# PROC054D_AWR_1_AWR_4_LP87524P.net
KiCad netlist of a schematic drawn in Altium Designer
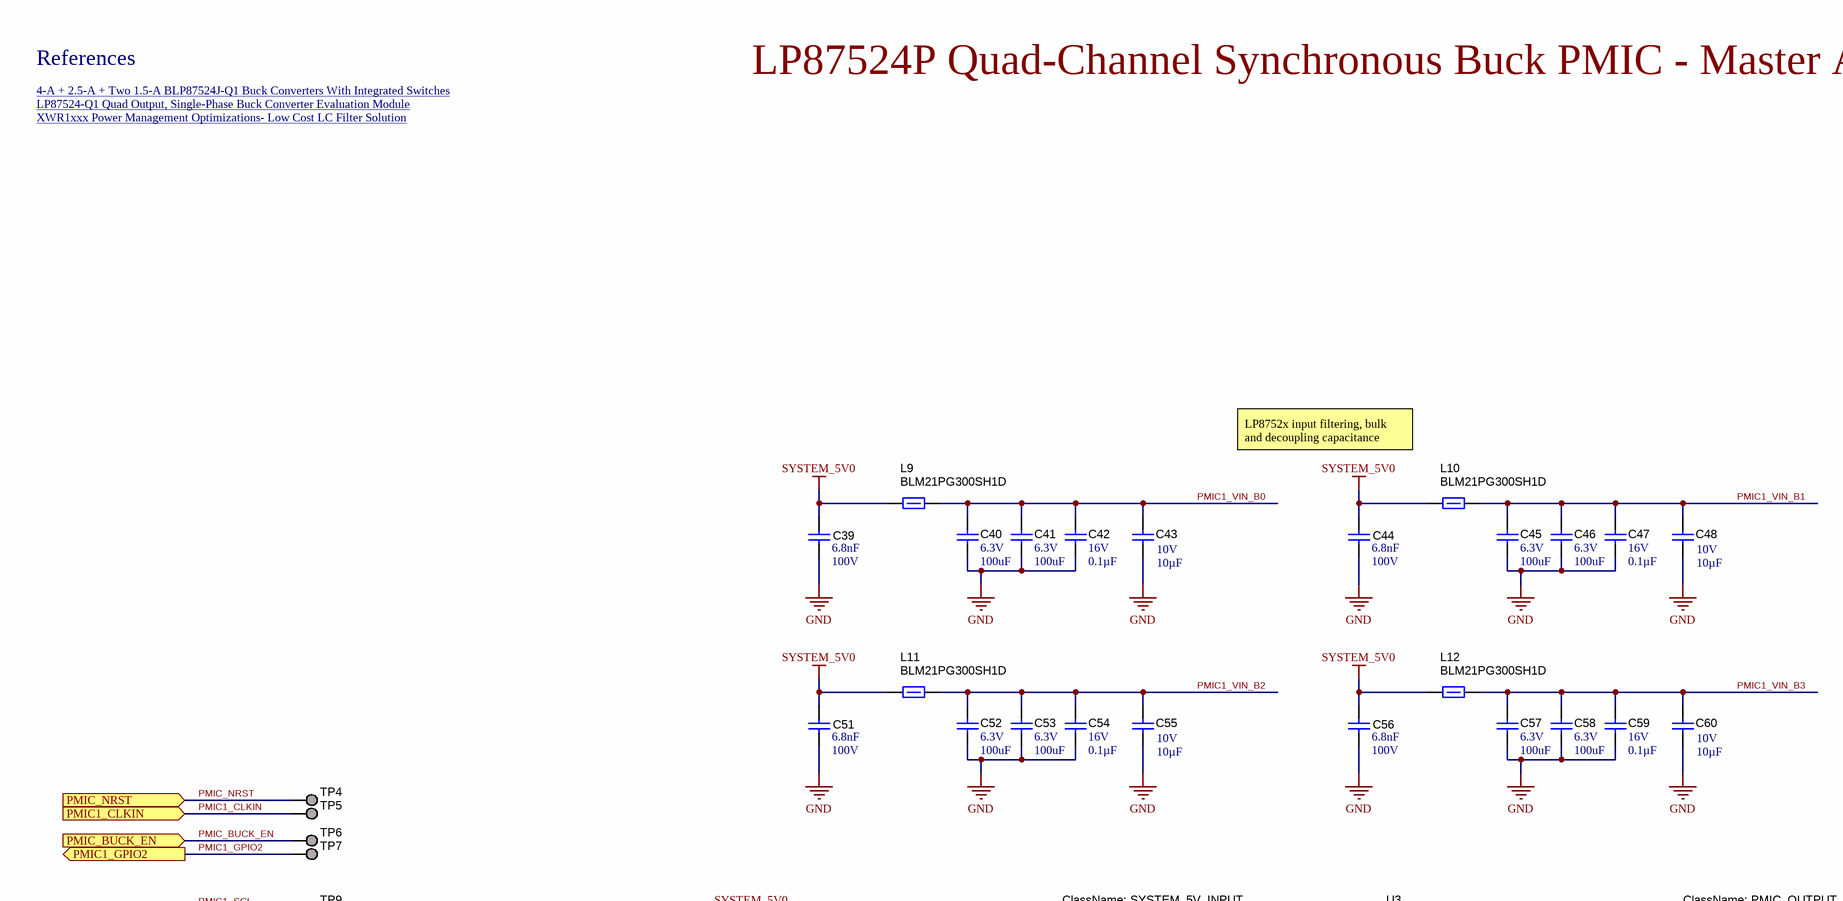
[diagram p0: PROC054D_AWR_1_AWR_4_LP87524P.SchDoc, top left]
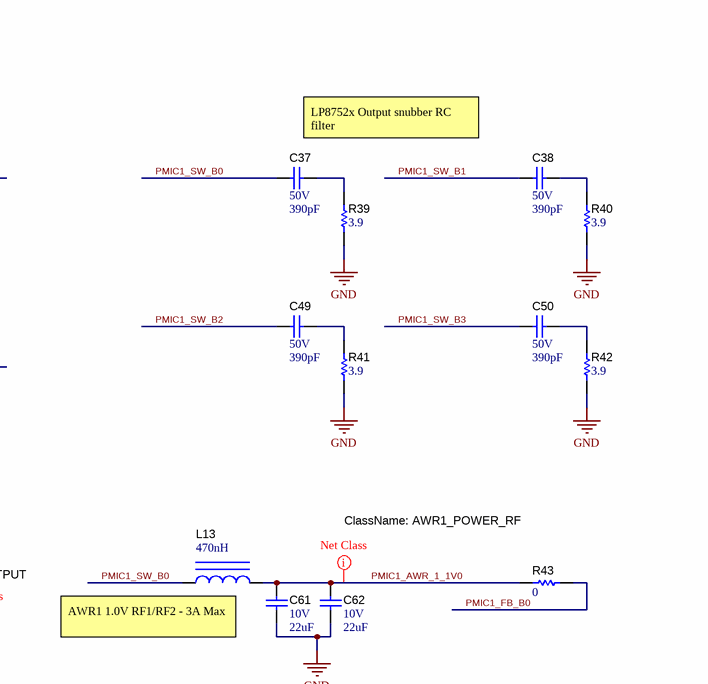
[diagram p1: PROC054D_AWR_1_AWR_4_LP87524P.SchDoc, top right]
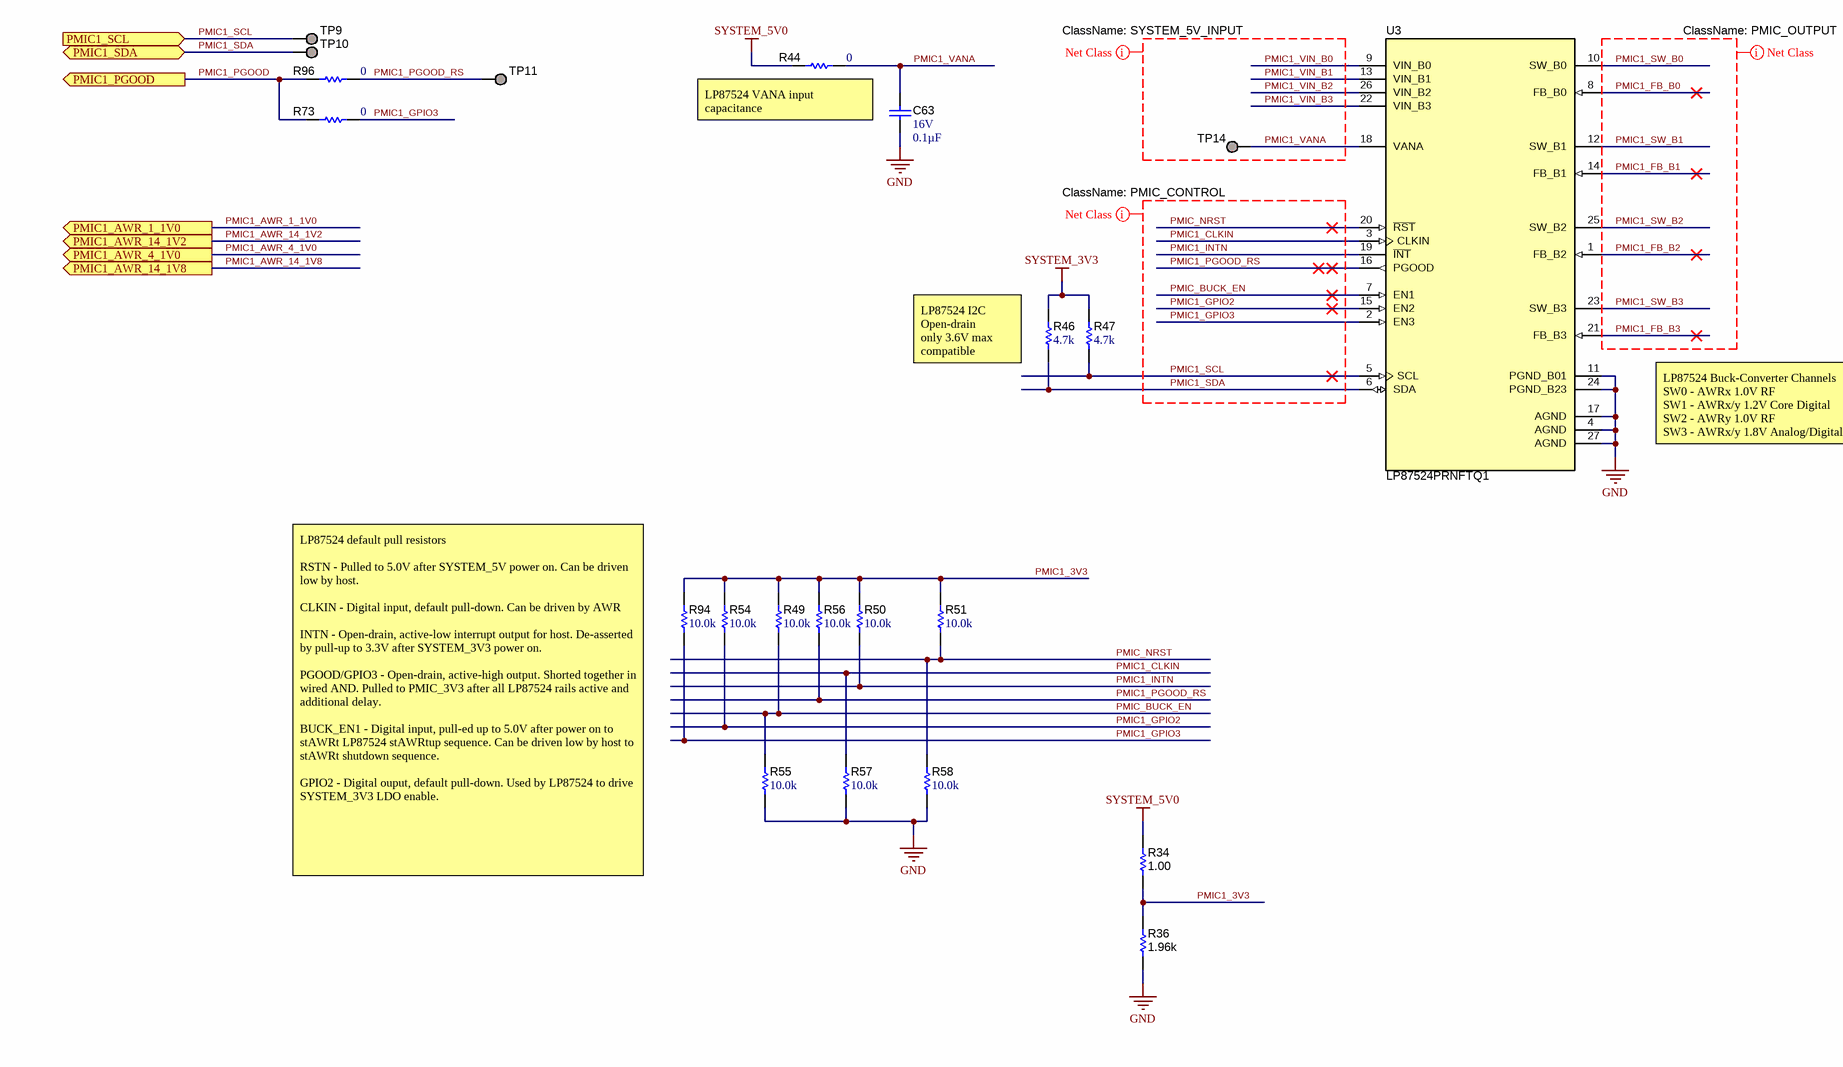
[diagram p2: PROC054D_AWR_1_AWR_4_LP87524P.SchDoc, bottom left]
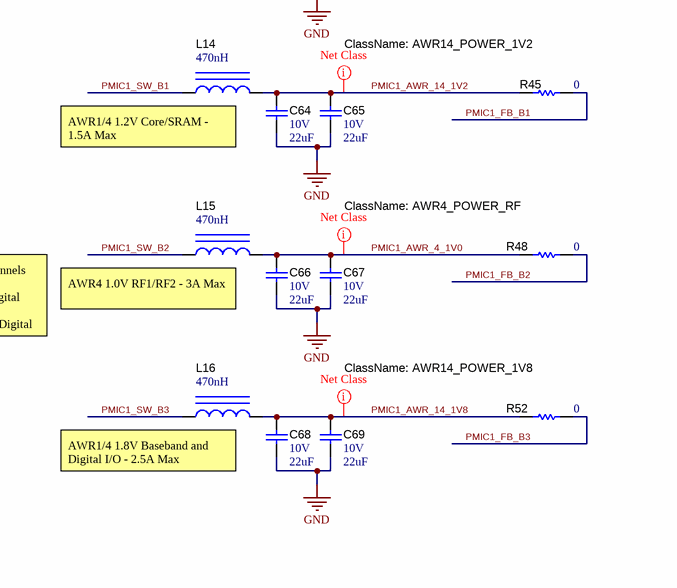
[diagram p3: PROC054D_AWR_1_AWR_4_LP87524P.SchDoc, bottom right]

(export (version "E")
  (design (tool "Eeschema 10.0.6"))
  (components
    (comp (ref "C37")
      (value "GCM155R71H391KA37D")
      (footprint "0402S")
      (description "CAP, CERM, 390 pF, 50 V,+/- 10%, X7R, AEC-Q200 Grade 1, 0402")
      (fields
        (field (name "MANUFACTURER") "MuRata")
        (field (name "VDC_V") "50V")
        (field (name "VALUEDISPLAYED") "390pF")
      )
      (libsource (lib "Altium Vault - TI") (part "Capacitor"))
    )
    (comp (ref "C38")
      (value "GCM155R71H391KA37D")
      (footprint "0402S")
      (description "CAP, CERM, 390 pF, 50 V,+/- 10%, X7R, AEC-Q200 Grade 1, 0402")
      (fields
        (field (name "MANUFACTURER") "MuRata")
        (field (name "VDC_V") "50V")
        (field (name "VALUEDISPLAYED") "390pF")
      )
      (libsource (lib "Altium Vault - TI") (part "Capacitor"))
    )
    (comp (ref "C39")
      (value "GCM188R72A682KA37D")
      (footprint "0603S")
      (description "CAP, CERM, 6800 pF, 100 V,+/- 10%, X7R, AEC-Q200 Grade 1, 0603")
      (fields
        (field (name "CAP_F") "6.8nF")
        (field (name "VDC_V") "100V")
        (field (name "MANUFACTURER") "MuRata")
      )
      (libsource (lib "Altium Vault - TI") (part "Capacitor"))
    )
    (comp (ref "C40")
      (value "GRM21BR60J107M")
      (footprint "0805L")
      (description "CAP, CERM, 100 uF, 6.3 V, +/- 20%, X5R, 0805")
      (fields
        (field (name "MANUFACTURER") "MuRata")
        (field (name "VDC_V") "6.3V")
        (field (name "VALUEDISPLAYED") "100uF")
        (field (name "PUBLISHER") "Texas Instruments")
      )
      (libsource (lib "Altium Vault - TI") (part "CMP-0008280-2"))
    )
    (comp (ref "C41")
      (value "GRM21BR60J107M")
      (footprint "0805L")
      (description "CAP, CERM, 100 uF, 6.3 V, +/- 20%, X5R, 0805")
      (fields
        (field (name "MANUFACTURER") "MuRata")
        (field (name "VDC_V") "6.3V")
        (field (name "VALUEDISPLAYED") "100uF")
        (field (name "PUBLISHER") "Texas Instruments")
      )
      (libsource (lib "Altium Vault - TI") (part "CMP-0008280-2"))
    )
    (comp (ref "C42")
      (value "GCM155R71C104JA55D")
      (footprint "0402S")
      (description "CAP, CERM, 0.1 µF, 16 V,+/- 5%, X7R, AEC-Q200 Grade 1, 0402")
      (fields
        (field (name "MANUFACTURER") "MuRata")
        (field (name "VDC_V") "16V")
        (field (name "VALUEDISPLAYED") "0.1µF")
      )
      (libsource (lib "Altium Vault - TI") (part "CMP-0080702-1"))
    )
    (comp (ref "C43")
      (value "GRM21BR71A106KA73L")
      (footprint "0805L")
      (description "CAP, CERM, 10 µF,  V,+/- 10%, X7R, 0805")
      (fields
        (field (name "MANUFACTURER") "MuRata")
        (field (name "CAP_F") "10µF")
        (field (name "VDC_V") "10V")
      )
      (libsource (lib "Altium Vault - TI") (part "Capacitor"))
    )
    (comp (ref "C44")
      (value "GCM188R72A682KA37D")
      (footprint "0603S")
      (description "CAP, CERM, 6800 pF, 100 V,+/- 10%, X7R, AEC-Q200 Grade 1, 0603")
      (fields
        (field (name "CAP_F") "6.8nF")
        (field (name "VDC_V") "100V")
        (field (name "MANUFACTURER") "MuRata")
      )
      (libsource (lib "Altium Vault - TI") (part "Capacitor"))
    )
    (comp (ref "C45")
      (value "GRM21BR60J107M")
      (footprint "0805L")
      (description "CAP, CERM, 100 uF, 6.3 V, +/- 20%, X5R, 0805")
      (fields
        (field (name "MANUFACTURER") "MuRata")
        (field (name "VDC_V") "6.3V")
        (field (name "VALUEDISPLAYED") "100uF")
        (field (name "PUBLISHER") "Texas Instruments")
      )
      (libsource (lib "Altium Vault - TI") (part "Capacitor"))
    )
    (comp (ref "C46")
      (value "GRM21BR60J107M")
      (footprint "0805L")
      (description "CAP, CERM, 100 uF, 6.3 V, +/- 20%, X5R, 0805")
      (fields
        (field (name "MANUFACTURER") "MuRata")
        (field (name "VDC_V") "6.3V")
        (field (name "VALUEDISPLAYED") "100uF")
        (field (name "PUBLISHER") "Texas Instruments")
      )
      (libsource (lib "Altium Vault - TI") (part "Capacitor"))
    )
    (comp (ref "C47")
      (value "GCM155R71C104JA55D")
      (footprint "0402S")
      (description "CAP, CERM, 0.1 µF, 16 V,+/- 5%, X7R, AEC-Q200 Grade 1, 0402")
      (fields
        (field (name "MANUFACTURER") "MuRata")
        (field (name "VDC_V") "16V")
        (field (name "VALUEDISPLAYED") "0.1µF")
      )
      (libsource (lib "Altium Vault - TI") (part "Capacitor"))
    )
    (comp (ref "C48")
      (value "GRM21BR71A106KA73L")
      (footprint "0805L")
      (description "CAP, CERM, 10 µF,  V,+/- 10%, X7R, 0805")
      (fields
        (field (name "MANUFACTURER") "MuRata")
        (field (name "CAP_F") "10µF")
        (field (name "VDC_V") "10V")
      )
      (libsource (lib "Altium Vault - TI") (part "Capacitor"))
    )
    (comp (ref "C49")
      (value "GCM155R71H391KA37D")
      (footprint "0402S")
      (description "CAP, CERM, 390 pF, 50 V,+/- 10%, X7R, AEC-Q200 Grade 1, 0402")
      (fields
        (field (name "MANUFACTURER") "MuRata")
        (field (name "VDC_V") "50V")
        (field (name "VALUEDISPLAYED") "390pF")
      )
      (libsource (lib "Altium Vault - TI") (part "Capacitor"))
    )
    (comp (ref "C50")
      (value "GCM155R71H391KA37D")
      (footprint "0402S")
      (description "CAP, CERM, 390 pF, 50 V,+/- 10%, X7R, AEC-Q200 Grade 1, 0402")
      (fields
        (field (name "MANUFACTURER") "MuRata")
        (field (name "VDC_V") "50V")
        (field (name "VALUEDISPLAYED") "390pF")
      )
      (libsource (lib "Altium Vault - TI") (part "Capacitor"))
    )
    (comp (ref "C51")
      (value "GCM188R72A682KA37D")
      (footprint "0603S")
      (description "CAP, CERM, 6800 pF, 100 V,+/- 10%, X7R, AEC-Q200 Grade 1, 0603")
      (fields
        (field (name "CAP_F") "6.8nF")
        (field (name "VDC_V") "100V")
        (field (name "MANUFACTURER") "MuRata")
      )
      (libsource (lib "Altium Vault - TI") (part "Capacitor"))
    )
    (comp (ref "C52")
      (value "GRM21BR60J107M")
      (footprint "0805L")
      (description "CAP, CERM, 100 uF, 6.3 V, +/- 20%, X5R, 0805")
      (fields
        (field (name "MANUFACTURER") "MuRata")
        (field (name "VDC_V") "6.3V")
        (field (name "VALUEDISPLAYED") "100uF")
        (field (name "PUBLISHER") "Texas Instruments")
      )
      (libsource (lib "Altium Vault - TI") (part "Capacitor"))
    )
    (comp (ref "C53")
      (value "GRM21BR60J107M")
      (footprint "0805L")
      (description "CAP, CERM, 100 uF, 6.3 V, +/- 20%, X5R, 0805")
      (fields
        (field (name "MANUFACTURER") "MuRata")
        (field (name "VDC_V") "6.3V")
        (field (name "VALUEDISPLAYED") "100uF")
        (field (name "PUBLISHER") "Texas Instruments")
      )
      (libsource (lib "Altium Vault - TI") (part "Capacitor"))
    )
    (comp (ref "C54")
      (value "GCM155R71C104JA55D")
      (footprint "0402S")
      (description "CAP, CERM, 0.1 µF, 16 V,+/- 5%, X7R, AEC-Q200 Grade 1, 0402")
      (fields
        (field (name "MANUFACTURER") "MuRata")
        (field (name "VDC_V") "16V")
        (field (name "VALUEDISPLAYED") "0.1µF")
      )
      (libsource (lib "Altium Vault - TI") (part "Capacitor"))
    )
    (comp (ref "C55")
      (value "GRM21BR71A106KA73L")
      (footprint "0805L")
      (description "CAP, CERM, 10 µF,  V,+/- 10%, X7R, 0805")
      (fields
        (field (name "MANUFACTURER") "MuRata")
        (field (name "CAP_F") "10µF")
        (field (name "VDC_V") "10V")
      )
      (libsource (lib "Altium Vault - TI") (part "Capacitor"))
    )
    (comp (ref "C56")
      (value "GCM188R72A682KA37D")
      (footprint "0603S")
      (description "CAP, CERM, 6800 pF, 100 V,+/- 10%, X7R, AEC-Q200 Grade 1, 0603")
      (fields
        (field (name "CAP_F") "6.8nF")
        (field (name "VDC_V") "100V")
        (field (name "MANUFACTURER") "MuRata")
      )
      (libsource (lib "Altium Vault - TI") (part "Capacitor"))
    )
    (comp (ref "C57")
      (value "GRM21BR60J107M")
      (footprint "0805L")
      (description "CAP, CERM, 100 uF, 6.3 V, +/- 20%, X5R, 0805")
      (fields
        (field (name "MANUFACTURER") "MuRata")
        (field (name "VDC_V") "6.3V")
        (field (name "VALUEDISPLAYED") "100uF")
        (field (name "PUBLISHER") "Texas Instruments")
      )
      (libsource (lib "Altium Vault - TI") (part "Capacitor"))
    )
    (comp (ref "C58")
      (value "GRM21BR60J107M")
      (footprint "0805L")
      (description "CAP, CERM, 100 uF, 6.3 V, +/- 20%, X5R, 0805")
      (fields
        (field (name "MANUFACTURER") "MuRata")
        (field (name "VDC_V") "6.3V")
        (field (name "VALUEDISPLAYED") "100uF")
        (field (name "PUBLISHER") "Texas Instruments")
      )
      (libsource (lib "Altium Vault - TI") (part "Capacitor"))
    )
    (comp (ref "C59")
      (value "GCM155R71C104JA55D")
      (footprint "0402S")
      (description "CAP, CERM, 0.1 µF, 16 V,+/- 5%, X7R, AEC-Q200 Grade 1, 0402")
      (fields
        (field (name "MANUFACTURER") "MuRata")
        (field (name "VDC_V") "16V")
        (field (name "VALUEDISPLAYED") "0.1µF")
      )
      (libsource (lib "Altium Vault - TI") (part "Capacitor"))
    )
    (comp (ref "C60")
      (value "GRM21BR71A106KA73L")
      (footprint "0805L")
      (description "CAP, CERM, 10 µF,  V,+/- 10%, X7R, 0805")
      (fields
        (field (name "MANUFACTURER") "MuRata")
        (field (name "CAP_F") "10µF")
        (field (name "VDC_V") "10V")
      )
      (libsource (lib "Altium Vault - TI") (part "Capacitor"))
    )
    (comp (ref "C61")
      (value "C2012X7S1A226M125AC")
      (footprint "0805L")
      (description "CAP, CERM, 22 uF, 10 V, +/- 20%, X7S, 0805")
      (fields
        (field (name "MANUFACTURER") "TDK")
        (field (name "VDC_V") "10V")
        (field (name "VALUEDISPLAYED") "22uF")
        (field (name "PUBLISHER") "Texas Instruments")
      )
      (libsource (lib "Altium Vault - TI") (part "Capacitor"))
    )
    (comp (ref "C62")
      (value "C2012X7S1A226M125AC")
      (footprint "0805L")
      (description "CAP, CERM, 22 uF, 10 V, +/- 20%, X7S, 0805")
      (fields
        (field (name "MANUFACTURER") "TDK")
        (field (name "VDC_V") "10V")
        (field (name "VALUEDISPLAYED") "22uF")
        (field (name "PUBLISHER") "Texas Instruments")
      )
      (libsource (lib "Altium Vault - TI") (part "Capacitor"))
    )
    (comp (ref "C63")
      (value "GCM155R71C104JA55D")
      (footprint "0402S")
      (description "CAP, CERM, 0.1 µF, 16 V,+/- 5%, X7R, AEC-Q200 Grade 1, 0402")
      (fields
        (field (name "MANUFACTURER") "MuRata")
        (field (name "VDC_V") "16V")
        (field (name "VALUEDISPLAYED") "0.1µF")
      )
      (libsource (lib "Altium Vault - TI") (part "CMP-0080702-1"))
    )
    (comp (ref "C64")
      (value "C2012X7S1A226M125AC")
      (footprint "0805L")
      (description "CAP, CERM, 22 uF, 10 V, +/- 20%, X7S, 0805")
      (fields
        (field (name "MANUFACTURER") "TDK")
        (field (name "VDC_V") "10V")
        (field (name "VALUEDISPLAYED") "22uF")
        (field (name "PUBLISHER") "Texas Instruments")
      )
      (libsource (lib "Altium Vault - TI") (part "Capacitor"))
    )
    (comp (ref "C65")
      (value "C2012X7S1A226M125AC")
      (footprint "0805L")
      (description "CAP, CERM, 22 uF, 10 V, +/- 20%, X7S, 0805")
      (fields
        (field (name "MANUFACTURER") "TDK")
        (field (name "VDC_V") "10V")
        (field (name "VALUEDISPLAYED") "22uF")
        (field (name "PUBLISHER") "Texas Instruments")
      )
      (libsource (lib "Altium Vault - TI") (part "Capacitor"))
    )
    (comp (ref "C66")
      (value "C2012X7S1A226M125AC")
      (footprint "0805L")
      (description "CAP, CERM, 22 uF, 10 V, +/- 20%, X7S, 0805")
      (fields
        (field (name "MANUFACTURER") "TDK")
        (field (name "VDC_V") "10V")
        (field (name "VALUEDISPLAYED") "22uF")
        (field (name "PUBLISHER") "Texas Instruments")
      )
      (libsource (lib "Altium Vault - TI") (part "Capacitor"))
    )
    (comp (ref "C67")
      (value "C2012X7S1A226M125AC")
      (footprint "0805L")
      (description "CAP, CERM, 22 uF, 10 V, +/- 20%, X7S, 0805")
      (fields
        (field (name "MANUFACTURER") "TDK")
        (field (name "VDC_V") "10V")
        (field (name "VALUEDISPLAYED") "22uF")
        (field (name "PUBLISHER") "Texas Instruments")
      )
      (libsource (lib "Altium Vault - TI") (part "Capacitor"))
    )
    (comp (ref "C68")
      (value "C2012X7S1A226M125AC")
      (footprint "0805L")
      (description "CAP, CERM, 22 uF, 10 V, +/- 20%, X7S, 0805")
      (fields
        (field (name "MANUFACTURER") "TDK")
        (field (name "VDC_V") "10V")
        (field (name "VALUEDISPLAYED") "22uF")
        (field (name "PUBLISHER") "Texas Instruments")
      )
      (libsource (lib "Altium Vault - TI") (part "Capacitor"))
    )
    (comp (ref "C69")
      (value "C2012X7S1A226M125AC")
      (footprint "0805L")
      (description "CAP, CERM, 22 uF, 10 V, +/- 20%, X7S, 0805")
      (fields
        (field (name "MANUFACTURER") "TDK")
        (field (name "VDC_V") "10V")
        (field (name "VALUEDISPLAYED") "22uF")
        (field (name "PUBLISHER") "Texas Instruments")
      )
      (libsource (lib "Altium Vault - TI") (part "Capacitor"))
    )
    (comp (ref "L9")
      (value "BLM21PG300SH1D")
      (footprint "0805_HV")
      (description "Ferrite Bead, 30 ohm @ 100 MHz, 4 A, 0805")
      (fields (field (name "MANUFACTURER") "MuRata") (field (name "PUBLISHER") "Texas Instruments"))
      (libsource (lib "Altium Vault - TI") (part "CMP-0003364-1"))
    )
    (comp (ref "L10")
      (value "BLM21PG300SH1D")
      (footprint "0805_HV")
      (description "Ferrite Bead, 30 ohm @ 100 MHz, 4 A, 0805")
      (fields (field (name "MANUFACTURER") "MuRata") (field (name "PUBLISHER") "Texas Instruments"))
      (libsource (lib "Altium Vault - TI") (part "Ferrite_Bead"))
    )
    (comp (ref "L11")
      (value "BLM21PG300SH1D")
      (footprint "0805_HV")
      (description "Ferrite Bead, 30 ohm @ 100 MHz, 4 A, 0805")
      (fields (field (name "MANUFACTURER") "MuRata") (field (name "PUBLISHER") "Texas Instruments"))
      (libsource (lib "Altium Vault - TI") (part "Ferrite_Bead"))
    )
    (comp (ref "L12")
      (value "BLM21PG300SH1D")
      (footprint "0805_HV")
      (description "Ferrite Bead, 30 ohm @ 100 MHz, 4 A, 0805")
      (fields (field (name "MANUFACTURER") "MuRata") (field (name "PUBLISHER") "Texas Instruments"))
      (libsource (lib "Altium Vault - TI") (part "Ferrite_Bead"))
    )
    (comp (ref "L13")
      (value "DFE252012PD-R47M")
      (footprint "DFE252012P")
      (description "Inductor, Shielded, 470 nH, 4.7 A, 0.021 ohm, SMD")
      (fields
        (field (name "MANUFACTURER") "MuRata Toko")
        (field (name "VALUEDISPLAYED") "470nH")
        (field (name "PUBLISHER") "Texas Instruments")
      )
      (libsource (lib "Altium Vault - TI") (part "Inductor_Iron"))
    )
    (comp (ref "L14")
      (value "DFE252012PD-R47M")
      (footprint "DFE252012P")
      (description "Inductor, Shielded, 470 nH, 4.7 A, 0.021 ohm, SMD")
      (fields
        (field (name "MANUFACTURER") "MuRata Toko")
        (field (name "VALUEDISPLAYED") "470nH")
        (field (name "PUBLISHER") "Texas Instruments")
      )
      (libsource (lib "Altium Vault - TI") (part "Inductor_Iron"))
    )
    (comp (ref "L15")
      (value "DFE252012PD-R47M")
      (footprint "DFE252012P")
      (description "Inductor, Shielded, 470 nH, 4.7 A, 0.021 ohm, SMD")
      (fields
        (field (name "MANUFACTURER") "MuRata Toko")
        (field (name "VALUEDISPLAYED") "470nH")
        (field (name "PUBLISHER") "Texas Instruments")
      )
      (libsource (lib "Altium Vault - TI") (part "Inductor_Iron"))
    )
    (comp (ref "L16")
      (value "DFE252012PD-R47M")
      (footprint "DFE252012P")
      (description "Inductor, Shielded, 470 nH, 4.7 A, 0.021 ohm, SMD")
      (fields
        (field (name "MANUFACTURER") "MuRata Toko")
        (field (name "VALUEDISPLAYED") "470nH")
        (field (name "PUBLISHER") "Texas Instruments")
      )
      (libsource (lib "Altium Vault - TI") (part "Inductor_Iron"))
    )
    (comp (ref "R34")
      (value "CRCW06031R00FKEA")
      (footprint "0603")
      (description "RES, 1.00, 1%, 0.1 W, AEC-Q200 Grade 0, 0603")
      (fields (field (name "MANUFACTURER") "Vishay-Dale") (field (name "VALUEDISPLAYED") "1.00"))
      (libsource (lib "Altium Vault - TI") (part "Resistor"))
    )
    (comp (ref "R36")
      (value "CRCW06031K96FKEA")
      (footprint "0603")
      (description "RES, 1.96 k, 1%, 0.1 W, AEC-Q200 Grade 0, 0603")
      (fields (field (name "MANUFACTURER") "Vishay-Dale") (field (name "VALUEDISPLAYED") "1.96k"))
      (libsource (lib "Altium Vault - TI") (part "Resistor"))
    )
    (comp (ref "R39")
      (value "CRCW04023R90JNED")
      (footprint "0402S")
      (description "RES, 3.9, 5%, 0.063 W, AEC-Q200 Grade 0, 0402")
      (fields (field (name "MANUFACTURER") "Vishay-Dale") (field (name "VALUEDISPLAYED") "3.9"))
      (libsource (lib "Altium Vault - TI") (part "CMP-0026928-3"))
    )
    (comp (ref "R40")
      (value "CRCW04023R90JNED")
      (footprint "0402S")
      (description "RES, 3.9, 5%, 0.063 W, AEC-Q200 Grade 0, 0402")
      (fields (field (name "MANUFACTURER") "Vishay-Dale") (field (name "VALUEDISPLAYED") "3.9"))
      (libsource (lib "Altium Vault - TI") (part "Resistor"))
    )
    (comp (ref "R41")
      (value "CRCW04023R90JNED")
      (footprint "0402S")
      (description "RES, 3.9, 5%, 0.063 W, AEC-Q200 Grade 0, 0402")
      (fields (field (name "MANUFACTURER") "Vishay-Dale") (field (name "VALUEDISPLAYED") "3.9"))
      (libsource (lib "Altium Vault - TI") (part "Resistor"))
    )
    (comp (ref "R42")
      (value "CRCW04023R90JNED")
      (footprint "0402S")
      (description "RES, 3.9, 5%, 0.063 W, AEC-Q200 Grade 0, 0402")
      (fields (field (name "MANUFACTURER") "Vishay-Dale") (field (name "VALUEDISPLAYED") "3.9"))
      (libsource (lib "Altium Vault - TI") (part "Resistor"))
    )
    (comp (ref "R43")
      (value "CRCW04020000Z0ED")
      (footprint "0402S")
      (description "RES, 0, 5%, 0.063 W, AEC-Q200 Grade 0, 0402")
      (fields (field (name "MANUFACTURER") "Vishay-Dale") (field (name "VALUEDISPLAYED") "0"))
      (libsource (lib "Altium Vault - TI") (part "Resistor"))
    )
    (comp (ref "R44")
      (value "MCT06030Z0000ZP500")
      (footprint "0603S")
      (description "RES, 0, 5%, 0.125 W, 0603")
      (fields
        (field (name "MANUFACTURER") "Vishay/Beyschlag")
        (field (name "VALUEDISPLAYED") "0")
        (field (name "PUBLISHER") "Texas Instruments")
      )
      (libsource (lib "Altium Vault - TI") (part "CMP-0025884-3"))
    )
    (comp (ref "R45")
      (value "CRCW04020000Z0ED")
      (footprint "0402S")
      (description "RES, 0, 5%, 0.063 W, AEC-Q200 Grade 0, 0402")
      (fields (field (name "MANUFACTURER") "Vishay-Dale") (field (name "VALUEDISPLAYED") "0"))
      (libsource (lib "Altium Vault - TI") (part "Resistor"))
    )
    (comp (ref "R46")
      (value "CRCW04024K70JNED")
      (footprint "0402")
      (description "RES, 4.7 k, 5%, 0.063 W, AEC-Q200 Grade 0, 0402")
      (fields (field (name "MANUFACTURER") "Vishay-Dale") (field (name "VALUEDISPLAYED") "4.7k"))
      (libsource (lib "Altium Vault - TI") (part "CMP-0026938-5"))
    )
    (comp (ref "R47")
      (value "CRCW04024K70JNED")
      (footprint "0402")
      (description "RES, 4.7 k, 5%, 0.063 W, AEC-Q200 Grade 0, 0402")
      (fields (field (name "MANUFACTURER") "Vishay-Dale") (field (name "VALUEDISPLAYED") "4.7k"))
      (libsource (lib "Altium Vault - TI") (part "Resistor"))
    )
    (comp (ref "R48")
      (value "CRCW04020000Z0ED")
      (footprint "0402S")
      (description "RES, 0, 5%, 0.063 W, AEC-Q200 Grade 0, 0402")
      (fields (field (name "MANUFACTURER") "Vishay-Dale") (field (name "VALUEDISPLAYED") "0"))
      (libsource (lib "Altium Vault - TI") (part "Resistor"))
    )
    (comp (ref "R49")
      (value "CRCW040210K0FKED")
      (footprint "0402")
      (description "RES, 10.0 k, 1%, 0.063 W, AEC-Q200 Grade 0, 0402")
      (fields (field (name "MANUFACTURER") "Vishay-Dale") (field (name "VALUEDISPLAYED") "10.0k"))
      (libsource (lib "Altium Vault - TI") (part "Resistor"))
    )
    (comp (ref "R50")
      (value "CRCW040210K0FKED")
      (footprint "0402")
      (description "RES, 10.0 k, 1%, 0.063 W, AEC-Q200 Grade 0, 0402")
      (fields (field (name "MANUFACTURER") "Vishay-Dale") (field (name "VALUEDISPLAYED") "10.0k"))
      (libsource (lib "Altium Vault - TI") (part "Resistor"))
    )
    (comp (ref "R51")
      (value "CRCW040210K0FKED")
      (footprint "0402")
      (description "RES, 10.0 k, 1%, 0.063 W, AEC-Q200 Grade 0, 0402")
      (fields (field (name "MANUFACTURER") "Vishay-Dale") (field (name "VALUEDISPLAYED") "10.0k"))
      (libsource (lib "Altium Vault - TI") (part "Resistor"))
    )
    (comp (ref "R52")
      (value "CRCW04020000Z0ED")
      (footprint "0402S")
      (description "RES, 0, 5%, 0.063 W, AEC-Q200 Grade 0, 0402")
      (fields (field (name "MANUFACTURER") "Vishay-Dale") (field (name "VALUEDISPLAYED") "0"))
      (libsource (lib "Altium Vault - TI") (part "Resistor"))
    )
    (comp (ref "R54")
      (value "CRCW040210K0FKED")
      (footprint "0402")
      (description "RES, 10.0 k, 1%, 0.063 W, AEC-Q200 Grade 0, 0402")
      (fields (field (name "MANUFACTURER") "Vishay-Dale") (field (name "VALUEDISPLAYED") "10.0k"))
      (libsource (lib "Altium Vault - TI") (part "Resistor"))
    )
    (comp (ref "R55")
      (value "CRCW040210K0FKED")
      (footprint "0402")
      (description "RES, 10.0 k, 1%, 0.063 W, AEC-Q200 Grade 0, 0402")
      (fields (field (name "MANUFACTURER") "Vishay-Dale") (field (name "VALUEDISPLAYED") "10.0k"))
      (libsource (lib "Altium Vault - TI") (part "Resistor"))
    )
    (comp (ref "R56")
      (value "CRCW040210K0FKED")
      (footprint "0402")
      (description "RES, 10.0 k, 1%, 0.063 W, AEC-Q200 Grade 0, 0402")
      (fields (field (name "MANUFACTURER") "Vishay-Dale") (field (name "VALUEDISPLAYED") "10.0k"))
      (libsource (lib "Altium Vault - TI") (part "Resistor"))
    )
    (comp (ref "R57")
      (value "CRCW040210K0FKED")
      (footprint "0402")
      (description "RES, 10.0 k, 1%, 0.063 W, AEC-Q200 Grade 0, 0402")
      (fields (field (name "MANUFACTURER") "Vishay-Dale") (field (name "VALUEDISPLAYED") "10.0k"))
      (libsource (lib "Altium Vault - TI") (part "Resistor"))
    )
    (comp (ref "R58")
      (value "CRCW040210K0FKED")
      (footprint "0402")
      (description "RES, 10.0 k, 1%, 0.063 W, AEC-Q200 Grade 0, 0402")
      (fields (field (name "MANUFACTURER") "Vishay-Dale") (field (name "VALUEDISPLAYED") "10.0k"))
      (libsource (lib "Altium Vault - TI") (part "Resistor"))
    )
    (comp (ref "R73")
      (value "MCT06030Z0000ZP500")
      (footprint "0603")
      (description "RES, 0, 5%, 0.125 W, 0603")
      (fields
        (field (name "MANUFACTURER") "Vishay/Beyschlag")
        (field (name "VALUEDISPLAYED") "0")
        (field (name "PUBLISHER") "Texas Instruments")
      )
      (libsource (lib "Altium Vault - TI") (part "Resistor"))
    )
    (comp (ref "R94")
      (value "CRCW040210K0FKED")
      (footprint "0402")
      (description "RES, 10.0 k, 1%, 0.063 W, AEC-Q200 Grade 0, 0402")
      (fields (field (name "MANUFACTURER") "Vishay-Dale") (field (name "VALUEDISPLAYED") "10.0k"))
      (libsource (lib "Altium Vault - TI") (part "Resistor"))
    )
    (comp (ref "R96")
      (value "MCT06030Z0000ZP500")
      (footprint "0603")
      (description "RES, 0, 5%, 0.125 W, 0603")
      (fields
        (field (name "MANUFACTURER") "Vishay/Beyschlag")
        (field (name "VALUEDISPLAYED") "0")
        (field (name "PUBLISHER") "Texas Instruments")
      )
      (libsource (lib "Altium Vault - TI") (part "Resistor"))
    )
    (comp (ref "TP4")
      (value "TP_SM_1MM")
      (footprint "TP_SM_1MM")
      (description "1mm Test Point, SMT")
      (fields (field (name "MANUFACTURER") "Any") (field (name "PUBLISHER") "Texas Instruments"))
      (libsource (lib "Altium Vault - TI") (part "CMP-0003825-1"))
    )
    (comp (ref "TP5")
      (value "TP_SM_1MM")
      (footprint "TP_SM_1MM")
      (description "1mm Test Point, SMT")
      (fields (field (name "MANUFACTURER") "Any") (field (name "PUBLISHER") "Texas Instruments"))
      (libsource (lib "Altium Vault - TI") (part "CMP-0003825-1"))
    )
    (comp (ref "TP6")
      (value "TP_SM_1MM")
      (footprint "TP_SM_1MM")
      (description "1mm Test Point, SMT")
      (fields (field (name "MANUFACTURER") "Any") (field (name "PUBLISHER") "Texas Instruments"))
      (libsource (lib "Altium Vault - TI") (part "CMP-0003825-1"))
    )
    (comp (ref "TP7")
      (value "TP_SM_1MM")
      (footprint "TP_SM_1MM")
      (description "1mm Test Point, SMT")
      (fields (field (name "MANUFACTURER") "Any") (field (name "PUBLISHER") "Texas Instruments"))
      (libsource (lib "Altium Vault - TI") (part "CMP-0003825-1"))
    )
    (comp (ref "TP9")
      (value "TP_SM_1MM")
      (footprint "TP_SM_1MM")
      (description "1mm Test Point, SMT")
      (fields (field (name "MANUFACTURER") "Any") (field (name "PUBLISHER") "Texas Instruments"))
      (libsource (lib "Altium Vault - TI") (part "CMP-0003825-1"))
    )
    (comp (ref "TP10")
      (value "TP_SM_1MM")
      (footprint "TP_SM_1MM")
      (description "1mm Test Point, SMT")
      (fields (field (name "MANUFACTURER") "Any") (field (name "PUBLISHER") "Texas Instruments"))
      (libsource (lib "Altium Vault - TI") (part "CMP-0003825-1"))
    )
    (comp (ref "TP11")
      (value "TP_SM_1MM")
      (footprint "TP_SM_1MM")
      (description "1mm Test Point, SMT")
      (fields (field (name "MANUFACTURER") "Any") (field (name "PUBLISHER") "Texas Instruments"))
      (libsource (lib "Altium Vault - TI") (part "CMP-0003825-1"))
    )
    (comp (ref "TP14")
      (value "TP_SM_1MM")
      (footprint "TP_SM_1MM")
      (description "1mm Test Point, SMT")
      (fields (field (name "MANUFACTURER") "Any") (field (name "PUBLISHER") "Texas Instruments"))
      (libsource (lib "Altium Vault - TI") (part "CMP-0003825-1"))
    )
    (comp (ref "U3")
      (value "LP87524PRNFTQ1")
      (footprint "RNF0026C")
      (description "4-A + 2.5-A + Two 1.5-A Buck Converters With Integrated Switches, RNF0026C (VQFN-HR-26)")
      (fields
        (field (name "ALTERNATE PARTNUMBER") "LP87524PRNFRQ1")
        (field (name "MANUFACTURER") "Texas Instruments")
        (field (name "PARTNUMBER") "LP87524PRNFTQ1")
      )
      (libsource (lib "Altium Vault - TI") (part "CMP-0083823-1"))
    )
  )
  (nets
    (net (code "1") (name "/PMIC1_3V3") (class "Default")
      (node (ref "R34") (pin "1") (pinfunction "1_1") (pintype "passive"))
      (node (ref "R36") (pin "2") (pinfunction "2_2") (pintype "passive"))
      (node (ref "R49") (pin "2") (pinfunction "2_2") (pintype "passive"))
      (node (ref "R50") (pin "2") (pinfunction "2_2") (pintype "passive"))
      (node (ref "R51") (pin "2") (pinfunction "2_2") (pintype "passive"))
      (node (ref "R54") (pin "2") (pinfunction "2_2") (pintype "passive"))
      (node (ref "R56") (pin "2") (pinfunction "2_2") (pintype "passive"))
      (node (ref "R94") (pin "2") (pinfunction "2_2") (pintype "passive"))
    )
    (net (code "2") (name "/PMIC1_AWR_1_1V0") (class "Default")
      (node (ref "C61") (pin "1") (pinfunction "1_1") (pintype "passive"))
      (node (ref "C62") (pin "1") (pinfunction "1_1") (pintype "passive"))
      (node (ref "L13") (pin "2") (pinfunction "2_2") (pintype "passive"))
      (node (ref "R43") (pin "1") (pinfunction "1_1") (pintype "passive"))
    )
    (net (code "3") (name "/PMIC1_AWR_4_1V0") (class "Default")
      (node (ref "C66") (pin "1") (pinfunction "1_1") (pintype "passive"))
      (node (ref "C67") (pin "1") (pinfunction "1_1") (pintype "passive"))
      (node (ref "L15") (pin "2") (pinfunction "2_2") (pintype "passive"))
      (node (ref "R48") (pin "1") (pinfunction "1_1") (pintype "passive"))
    )
    (net (code "4") (name "/PMIC1_AWR_14_1V2") (class "Default")
      (node (ref "C64") (pin "1") (pinfunction "1_1") (pintype "passive"))
      (node (ref "C65") (pin "1") (pinfunction "1_1") (pintype "passive"))
      (node (ref "L14") (pin "2") (pinfunction "2_2") (pintype "passive"))
      (node (ref "R45") (pin "1") (pinfunction "1_1") (pintype "passive"))
    )
    (net (code "5") (name "/PMIC1_AWR_14_1V8") (class "Default")
      (node (ref "C68") (pin "1") (pinfunction "1_1") (pintype "passive"))
      (node (ref "C69") (pin "1") (pinfunction "1_1") (pintype "passive"))
      (node (ref "L16") (pin "2") (pinfunction "2_2") (pintype "passive"))
      (node (ref "R52") (pin "1") (pinfunction "1_1") (pintype "passive"))
    )
    (net (code "6") (name "/PMIC1_CLKIN") (class "Default")
      (node (ref "R57") (pin "2") (pinfunction "2_2") (pintype "passive"))
      (node (ref "TP5") (pin "1") (pintype "passive"))
      (node (ref "U3") (pin "3") (pinfunction "CLKIN_3") (pintype "input"))
    )
    (net (code "7") (name "/PMIC1_FB_B0") (class "Default")
      (node (ref "R43") (pin "2") (pinfunction "2_2") (pintype "passive"))
      (node (ref "U3") (pin "8") (pinfunction "FB_B0_8") (pintype "input"))
    )
    (net (code "8") (name "/PMIC1_FB_B1") (class "Default")
      (node (ref "R45") (pin "2") (pinfunction "2_2") (pintype "passive"))
      (node (ref "U3") (pin "14") (pinfunction "FB_B1_14") (pintype "input"))
    )
    (net (code "9") (name "/PMIC1_FB_B2") (class "Default")
      (node (ref "R48") (pin "2") (pinfunction "2_2") (pintype "passive"))
      (node (ref "U3") (pin "1") (pinfunction "FB_B2_1") (pintype "input"))
    )
    (net (code "10") (name "/PMIC1_FB_B3") (class "Default")
      (node (ref "R52") (pin "2") (pinfunction "2_2") (pintype "passive"))
      (node (ref "U3") (pin "21") (pinfunction "FB_B3_21") (pintype "input"))
    )
    (net (code "11") (name "/PMIC1_GPIO2") (class "Default")
      (node (ref "R54") (pin "1") (pinfunction "1_1") (pintype "passive"))
      (node (ref "TP7") (pin "1") (pintype "passive"))
      (node (ref "U3") (pin "15") (pinfunction "EN2_15") (pintype "input"))
    )
    (net (code "12") (name "/PMIC1_GPIO3") (class "Default")
      (node (ref "R73") (pin "2") (pinfunction "2_2") (pintype "passive"))
      (node (ref "R94") (pin "1") (pinfunction "1_1") (pintype "passive"))
      (node (ref "U3") (pin "2") (pinfunction "EN3_2") (pintype "input"))
    )
    (net (code "13") (name "/PMIC1_INTN") (class "Default")
      (node (ref "R50") (pin "1") (pinfunction "1_1") (pintype "passive"))
      (node (ref "U3") (pin "19") (pinfunction "INT_19") (pintype "open_collector"))
    )
    (net (code "14") (name "/PMIC1_PGOOD") (class "Default")
      (node (ref "R73") (pin "1") (pinfunction "1_1") (pintype "passive"))
      (node (ref "R96") (pin "1") (pinfunction "1_1") (pintype "passive"))
    )
    (net (code "15") (name "/PMIC1_PGOOD_RS") (class "Default")
      (node (ref "R56") (pin "1") (pinfunction "1_1") (pintype "passive"))
      (node (ref "R96") (pin "2") (pinfunction "2_2") (pintype "passive"))
      (node (ref "TP11") (pin "1") (pintype "passive"))
      (node (ref "U3") (pin "16") (pinfunction "PGOOD_16") (pintype "output"))
    )
    (net (code "16") (name "/PMIC1_SCL") (class "Default")
      (node (ref "R47") (pin "1") (pinfunction "1_1") (pintype "passive"))
      (node (ref "TP9") (pin "1") (pintype "passive"))
      (node (ref "U3") (pin "5") (pinfunction "SCL_5") (pintype "input"))
    )
    (net (code "17") (name "/PMIC1_SDA") (class "Default")
      (node (ref "R46") (pin "2") (pinfunction "2_2") (pintype "passive"))
      (node (ref "TP10") (pin "1") (pintype "passive"))
      (node (ref "U3") (pin "6") (pinfunction "SDA_6") (pintype "bidirectional"))
    )
    (net (code "18") (name "/PMIC1_SW_B0") (class "Default")
      (node (ref "C37") (pin "1") (pinfunction "1_1") (pintype "passive"))
      (node (ref "L13") (pin "1") (pinfunction "1_1") (pintype "passive"))
      (node (ref "U3") (pin "10") (pinfunction "SW_B0_10") (pintype "power_in"))
    )
    (net (code "19") (name "/PMIC1_SW_B1") (class "Default")
      (node (ref "C38") (pin "1") (pinfunction "1_1") (pintype "passive"))
      (node (ref "L14") (pin "1") (pinfunction "1_1") (pintype "passive"))
      (node (ref "U3") (pin "12") (pinfunction "SW_B1_12") (pintype "power_in"))
    )
    (net (code "20") (name "/PMIC1_SW_B2") (class "Default")
      (node (ref "C49") (pin "1") (pinfunction "1_1") (pintype "passive"))
      (node (ref "L15") (pin "1") (pinfunction "1_1") (pintype "passive"))
      (node (ref "U3") (pin "25") (pinfunction "SW_B2_25") (pintype "power_in"))
    )
    (net (code "21") (name "/PMIC1_SW_B3") (class "Default")
      (node (ref "C50") (pin "1") (pinfunction "1_1") (pintype "passive"))
      (node (ref "L16") (pin "1") (pinfunction "1_1") (pintype "passive"))
      (node (ref "U3") (pin "23") (pinfunction "SW_B3_23") (pintype "power_in"))
    )
    (net (code "22") (name "/PMIC1_VANA") (class "Default")
      (node (ref "C63") (pin "1") (pinfunction "1_1") (pintype "passive"))
      (node (ref "R44") (pin "2") (pinfunction "2_2") (pintype "passive"))
      (node (ref "TP14") (pin "1") (pintype "passive"))
      (node (ref "U3") (pin "18") (pinfunction "VANA_18") (pintype "power_in"))
    )
    (net (code "23") (name "/PMIC1_VIN_B0") (class "Default")
      (node (ref "C40") (pin "1") (pinfunction "1_1") (pintype "passive"))
      (node (ref "C41") (pin "1") (pinfunction "1_1") (pintype "passive"))
      (node (ref "C42") (pin "1") (pinfunction "1_1") (pintype "passive"))
      (node (ref "C43") (pin "1") (pinfunction "1_1") (pintype "passive"))
      (node (ref "L9") (pin "2") (pinfunction "2_2") (pintype "passive"))
      (node (ref "U3") (pin "9") (pinfunction "VIN_B0_9") (pintype "power_in"))
    )
    (net (code "24") (name "/PMIC1_VIN_B1") (class "Default")
      (node (ref "C45") (pin "1") (pinfunction "1_1") (pintype "passive"))
      (node (ref "C46") (pin "1") (pinfunction "1_1") (pintype "passive"))
      (node (ref "C47") (pin "1") (pinfunction "1_1") (pintype "passive"))
      (node (ref "C48") (pin "1") (pinfunction "1_1") (pintype "passive"))
      (node (ref "L10") (pin "2") (pinfunction "2_2") (pintype "passive"))
      (node (ref "U3") (pin "13") (pinfunction "VIN_B1_13") (pintype "power_in"))
    )
    (net (code "25") (name "/PMIC1_VIN_B2") (class "Default")
      (node (ref "C52") (pin "1") (pinfunction "1_1") (pintype "passive"))
      (node (ref "C53") (pin "1") (pinfunction "1_1") (pintype "passive"))
      (node (ref "C54") (pin "1") (pinfunction "1_1") (pintype "passive"))
      (node (ref "C55") (pin "1") (pinfunction "1_1") (pintype "passive"))
      (node (ref "L11") (pin "2") (pinfunction "2_2") (pintype "passive"))
      (node (ref "U3") (pin "26") (pinfunction "VIN_B2_26") (pintype "power_in"))
    )
    (net (code "26") (name "/PMIC1_VIN_B3") (class "Default")
      (node (ref "C57") (pin "1") (pinfunction "1_1") (pintype "passive"))
      (node (ref "C58") (pin "1") (pinfunction "1_1") (pintype "passive"))
      (node (ref "C59") (pin "1") (pinfunction "1_1") (pintype "passive"))
      (node (ref "C60") (pin "1") (pinfunction "1_1") (pintype "passive"))
      (node (ref "L12") (pin "2") (pinfunction "2_2") (pintype "passive"))
      (node (ref "U3") (pin "22") (pinfunction "VIN_B3_22") (pintype "power_in"))
    )
    (net (code "27") (name "/PMIC_BUCK_EN") (class "Default")
      (node (ref "R49") (pin "1") (pinfunction "1_1") (pintype "passive"))
      (node (ref "R55") (pin "2") (pinfunction "2_2") (pintype "passive"))
      (node (ref "TP6") (pin "1") (pintype "passive"))
      (node (ref "U3") (pin "7") (pinfunction "EN1_7") (pintype "input"))
    )
    (net (code "28") (name "/PMIC_NRST") (class "Default")
      (node (ref "R51") (pin "1") (pinfunction "1_1") (pintype "passive"))
      (node (ref "R58") (pin "2") (pinfunction "2_2") (pintype "passive"))
      (node (ref "TP4") (pin "1") (pintype "passive"))
      (node (ref "U3") (pin "20") (pinfunction "RST_20") (pintype "input"))
    )
    (net (code "29") (name "GND") (class "Default")
      (node (ref "C39") (pin "2") (pinfunction "2_2") (pintype "passive"))
      (node (ref "C40") (pin "2") (pinfunction "2_2") (pintype "passive"))
      (node (ref "C41") (pin "2") (pinfunction "2_2") (pintype "passive"))
      (node (ref "C42") (pin "2") (pinfunction "2_2") (pintype "passive"))
      (node (ref "C43") (pin "2") (pinfunction "2_2") (pintype "passive"))
      (node (ref "C44") (pin "2") (pinfunction "2_2") (pintype "passive"))
      (node (ref "C45") (pin "2") (pinfunction "2_2") (pintype "passive"))
      (node (ref "C46") (pin "2") (pinfunction "2_2") (pintype "passive"))
      (node (ref "C47") (pin "2") (pinfunction "2_2") (pintype "passive"))
      (node (ref "C48") (pin "2") (pinfunction "2_2") (pintype "passive"))
      (node (ref "C51") (pin "2") (pinfunction "2_2") (pintype "passive"))
      (node (ref "C52") (pin "2") (pinfunction "2_2") (pintype "passive"))
      (node (ref "C53") (pin "2") (pinfunction "2_2") (pintype "passive"))
      (node (ref "C54") (pin "2") (pinfunction "2_2") (pintype "passive"))
      (node (ref "C55") (pin "2") (pinfunction "2_2") (pintype "passive"))
      (node (ref "C56") (pin "2") (pinfunction "2_2") (pintype "passive"))
      (node (ref "C57") (pin "2") (pinfunction "2_2") (pintype "passive"))
      (node (ref "C58") (pin "2") (pinfunction "2_2") (pintype "passive"))
      (node (ref "C59") (pin "2") (pinfunction "2_2") (pintype "passive"))
      (node (ref "C60") (pin "2") (pinfunction "2_2") (pintype "passive"))
      (node (ref "C61") (pin "2") (pinfunction "2_2") (pintype "passive"))
      (node (ref "C62") (pin "2") (pinfunction "2_2") (pintype "passive"))
      (node (ref "C63") (pin "2") (pinfunction "2_2") (pintype "passive"))
      (node (ref "C64") (pin "2") (pinfunction "2_2") (pintype "passive"))
      (node (ref "C65") (pin "2") (pinfunction "2_2") (pintype "passive"))
      (node (ref "C66") (pin "2") (pinfunction "2_2") (pintype "passive"))
      (node (ref "C67") (pin "2") (pinfunction "2_2") (pintype "passive"))
      (node (ref "C68") (pin "2") (pinfunction "2_2") (pintype "passive"))
      (node (ref "C69") (pin "2") (pinfunction "2_2") (pintype "passive"))
      (node (ref "R36") (pin "1") (pinfunction "1_1") (pintype "passive"))
      (node (ref "R39") (pin "1") (pinfunction "1_1") (pintype "passive"))
      (node (ref "R40") (pin "1") (pinfunction "1_1") (pintype "passive"))
      (node (ref "R41") (pin "1") (pinfunction "1_1") (pintype "passive"))
      (node (ref "R42") (pin "1") (pinfunction "1_1") (pintype "passive"))
      (node (ref "R55") (pin "1") (pinfunction "1_1") (pintype "passive"))
      (node (ref "R57") (pin "1") (pinfunction "1_1") (pintype "passive"))
      (node (ref "R58") (pin "1") (pinfunction "1_1") (pintype "passive"))
      (node (ref "U3") (pin "11") (pinfunction "PGND_B01_11") (pintype "power_in"))
      (node (ref "U3") (pin "17") (pinfunction "AGND_17") (pintype "power_in"))
      (node (ref "U3") (pin "24") (pinfunction "PGND_B23_24") (pintype "power_in"))
      (node (ref "U3") (pin "27") (pinfunction "AGND_27") (pintype "power_in"))
      (node (ref "U3") (pin "4") (pinfunction "AGND_4") (pintype "power_in"))
    )
    (net (code "30") (name "Net-(C37-Pad2)") (class "Default")
      (node (ref "C37") (pin "2") (pinfunction "2_2") (pintype "passive"))
      (node (ref "R39") (pin "2") (pinfunction "2_2") (pintype "passive"))
    )
    (net (code "31") (name "Net-(C38-Pad2)") (class "Default")
      (node (ref "C38") (pin "2") (pinfunction "2_2") (pintype "passive"))
      (node (ref "R40") (pin "2") (pinfunction "2_2") (pintype "passive"))
    )
    (net (code "32") (name "Net-(C49-Pad2)") (class "Default")
      (node (ref "C49") (pin "2") (pinfunction "2_2") (pintype "passive"))
      (node (ref "R41") (pin "2") (pinfunction "2_2") (pintype "passive"))
    )
    (net (code "33") (name "Net-(C50-Pad2)") (class "Default")
      (node (ref "C50") (pin "2") (pinfunction "2_2") (pintype "passive"))
      (node (ref "R42") (pin "2") (pinfunction "2_2") (pintype "passive"))
    )
    (net (code "34") (name "SYSTEM_3V3") (class "Default")
      (node (ref "R46") (pin "1") (pinfunction "1_1") (pintype "passive"))
      (node (ref "R47") (pin "2") (pinfunction "2_2") (pintype "passive"))
    )
    (net (code "35") (name "SYSTEM_5V0") (class "Default")
      (node (ref "C39") (pin "1") (pinfunction "1_1") (pintype "passive"))
      (node (ref "C44") (pin "1") (pinfunction "1_1") (pintype "passive"))
      (node (ref "C51") (pin "1") (pinfunction "1_1") (pintype "passive"))
      (node (ref "C56") (pin "1") (pinfunction "1_1") (pintype "passive"))
      (node (ref "L10") (pin "1") (pinfunction "1_1") (pintype "passive"))
      (node (ref "L11") (pin "1") (pinfunction "1_1") (pintype "passive"))
      (node (ref "L12") (pin "1") (pinfunction "1_1") (pintype "passive"))
      (node (ref "L9") (pin "1") (pinfunction "1_1") (pintype "passive"))
      (node (ref "R34") (pin "2") (pinfunction "2_2") (pintype "passive"))
      (node (ref "R44") (pin "1") (pinfunction "1_1") (pintype "passive"))
    )
  )
)
